# Power.net
KiCad netlist of a schematic drawn in Altium Designer
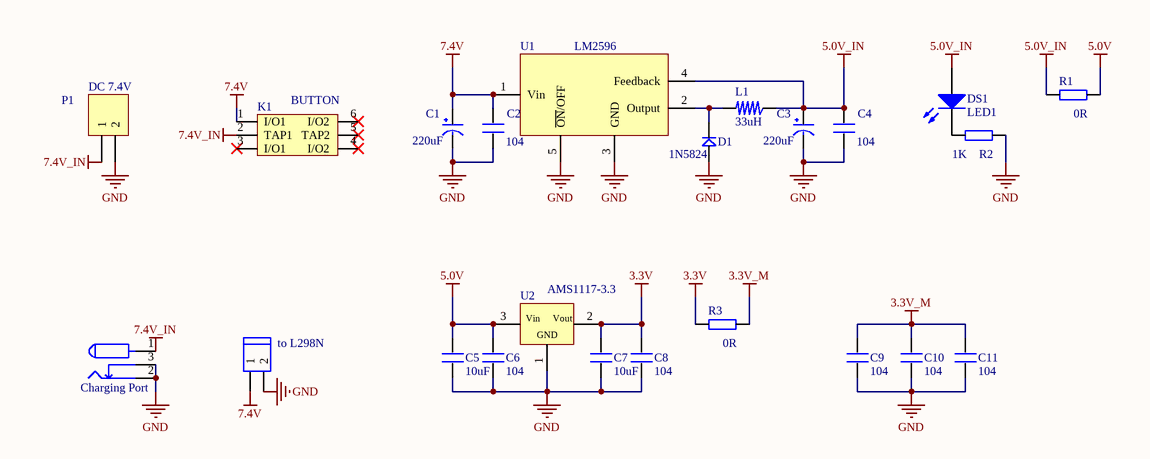
[diagram p0: Power.SchDoc]

(export (version "E")
  (design (tool "Eeschema 10.0.6"))
  (components
    (comp (ref "C1")
      (value "220uF")
      (footprint "CC6.56.5")
      (libsource (lib "WarShip V3 STM32103封装库") (part "CAP"))
    )
    (comp (ref "C2") (value "104") (footprint "0603P") (libsource (lib "WarShip V3 STM32103封装库") (part "C")))
    (comp (ref "C3")
      (value "220uF")
      (footprint "CC6.56.5")
      (libsource (lib "WarShip V3 STM32103封装库") (part "CAP"))
    )
    (comp (ref "C4") (value "104") (footprint "0603P") (libsource (lib "WarShip V3 STM32103封装库") (part "C")))
    (comp (ref "C5") (value "10uF") (footprint "0603P") (libsource (lib "WarShip V3 STM32103封装库") (part "C")))
    (comp (ref "C6") (value "104") (footprint "0603P") (libsource (lib "WarShip V3 STM32103封装库") (part "C")))
    (comp (ref "C7") (value "10uF") (footprint "0603P") (libsource (lib "WarShip V3 STM32103封装库") (part "C")))
    (comp (ref "C8") (value "104") (footprint "0603P") (libsource (lib "WarShip V3 STM32103封装库") (part "C")))
    (comp (ref "C9") (value "104") (footprint "0603P") (libsource (lib "WarShip V3 STM32103封装库") (part "C")))
    (comp (ref "C10") (value "104") (footprint "0603P") (libsource (lib "WarShip V3 STM32103封装库") (part "C")))
    (comp (ref "C11") (value "104") (footprint "0603P") (libsource (lib "WarShip V3 STM32103封装库") (part "C")))
    (comp (ref "D1")
      (value "1N5824")
      (footprint "DIODE_SOP")
      (libsource (lib "WarShip V3 STM32103封装库") (part "D"))
    )
    (comp (ref "DC_IN1")
      (value "Charging Port")
      (footprint "DC10B")
      (libsource (lib "WarShip V3 STM32103封装库") (part "POW"))
    )
    (comp (ref "DS1")
      (value "LED1")
      (footprint "SMDLED")
      (description "Typical RED, GREEN, YELLOW, AMBER GaAs LED")
      (fields (field (name "PUBLISHER") "Altium Limited"))
      (libsource (lib "WarShip V3 STM32103封装库") (part "LED2"))
    )
    (comp (ref "K1")
      (value "BUTTON")
      (footprint "BTN8.5*8.5")
      (libsource (lib "WarShip V3 STM32103封装库") (part "BUTTON"))
    )
    (comp (ref "L1") (value "33uH") (footprint "CD54") (libsource (lib "Zink_LIB") (part "L")))
    (comp (ref "P1")
      (value "DC 7.4V")
      (footprint "XH2.54-2P")
      (description "Header, 2-Pin")
      (libsource (lib "Zink_LIB") (part "Header-2"))
    )
    (comp (ref "R1") (value "0R") (footprint "0603P") (libsource (lib "WarShip V3 STM32103封装库") (part "R")))
    (comp (ref "R2") (value "1K") (footprint "0603P") (libsource (lib "WarShip V3 STM32103封装库") (part "R")))
    (comp (ref "R3") (value "0R") (footprint "0603P") (libsource (lib "WarShip V3 STM32103封装库") (part "R")))
    (comp (ref "RS1")
      (value "to L298N")
      (footprint "HEAD2L-0.8")
      (libsource (lib "WarShip V3 STM32103封装库") (part "HEAD2"))
    )
    (comp (ref "U1")
      (value "LM2596")
      (footprint "TO-263-5")
      (description "LM2596 - 5.0")
      (libsource (lib "Zink_LIB") (part "LM2596"))
    )
    (comp (ref "U2")
      (value "AMS1117-3.3")
      (footprint "SOT223-4L")
      (libsource (lib "Zink_LIB") (part "AMS1117"))
    )
  )
  (nets
    (net (code "1") (name "3.3V") (class "Default")
      (node (ref "C7") (pin "2") (pintype "passive"))
      (node (ref "C8") (pin "2") (pintype "passive"))
      (node (ref "R3") (pin "1") (pintype "passive"))
      (node (ref "U2") (pin "2") (pinfunction "Vout_2") (pintype "passive"))
    )
    (net (code "2") (name "3.3V_M") (class "Default")
      (node (ref "C10") (pin "2") (pintype "passive"))
      (node (ref "C11") (pin "2") (pintype "passive"))
      (node (ref "C9") (pin "2") (pintype "passive"))
      (node (ref "R3") (pin "2") (pintype "passive"))
    )
    (net (code "3") (name "5.0V") (class "Default")
      (node (ref "C5") (pin "2") (pintype "passive"))
      (node (ref "C6") (pin "2") (pintype "passive"))
      (node (ref "R1") (pin "2") (pintype "passive"))
      (node (ref "U2") (pin "3") (pinfunction "Vin_3") (pintype "passive"))
    )
    (net (code "4") (name "5.0V_IN") (class "Default")
      (node (ref "C3") (pin "1") (pinfunction "VCC_1") (pintype "passive"))
      (node (ref "C4") (pin "2") (pintype "passive"))
      (node (ref "DS1") (pin "1") (pinfunction "A_1") (pintype "passive"))
      (node (ref "L1") (pin "2") (pinfunction "2_2") (pintype "passive"))
      (node (ref "R1") (pin "1") (pintype "passive"))
      (node (ref "U1") (pin "4") (pinfunction "Feedback_4") (pintype "passive"))
    )
    (net (code "5") (name "7.4V") (class "Default")
      (node (ref "C1") (pin "1") (pinfunction "VCC_1") (pintype "passive"))
      (node (ref "C2") (pin "2") (pintype "passive"))
      (node (ref "K1") (pin "1") (pinfunction "I/O1_1") (pintype "passive"))
      (node (ref "RS1") (pin "1") (pinfunction "1_1") (pintype "passive"))
      (node (ref "U1") (pin "1") (pinfunction "Vin_1") (pintype "passive"))
    )
    (net (code "6") (name "7.4V_IN") (class "Default")
      (node (ref "DC_IN1") (pin "1") (pintype "passive"))
      (node (ref "K1") (pin "2") (pinfunction "TAP1_2") (pintype "passive"))
      (node (ref "P1") (pin "1") (pinfunction "1_1") (pintype "passive"))
    )
    (net (code "7") (name "GND") (class "Default")
      (node (ref "C1") (pin "2") (pinfunction "GND_2") (pintype "passive"))
      (node (ref "C10") (pin "1") (pintype "passive"))
      (node (ref "C11") (pin "1") (pintype "passive"))
      (node (ref "C2") (pin "1") (pintype "passive"))
      (node (ref "C3") (pin "2") (pinfunction "GND_2") (pintype "passive"))
      (node (ref "C4") (pin "1") (pintype "passive"))
      (node (ref "C5") (pin "1") (pintype "passive"))
      (node (ref "C6") (pin "1") (pintype "passive"))
      (node (ref "C7") (pin "1") (pintype "passive"))
      (node (ref "C8") (pin "1") (pintype "passive"))
      (node (ref "C9") (pin "1") (pintype "passive"))
      (node (ref "D1") (pin "1") (pintype "passive"))
      (node (ref "DC_IN1") (pin "2") (pintype "passive"))
      (node (ref "DC_IN1") (pin "3") (pintype "passive"))
      (node (ref "P1") (pin "2") (pinfunction "2_2") (pintype "passive"))
      (node (ref "R2") (pin "2") (pintype "passive"))
      (node (ref "RS1") (pin "2") (pinfunction "2_2") (pintype "passive"))
      (node (ref "U1") (pin "3") (pinfunction "GND_3") (pintype "passive"))
      (node (ref "U1") (pin "5") (pinfunction "~{ON}/OFF_5") (pintype "passive"))
      (node (ref "U2") (pin "1") (pinfunction "GND_1") (pintype "passive"))
    )
    (net (code "8") (name "Net-(DS1-K)") (class "Default")
      (node (ref "DS1") (pin "2") (pinfunction "K_2") (pintype "passive"))
      (node (ref "R2") (pin "1") (pintype "passive"))
    )
    (net (code "9") (name "Net-(U1-Output)") (class "Default")
      (node (ref "D1") (pin "2") (pintype "passive"))
      (node (ref "L1") (pin "1") (pinfunction "1_1") (pintype "passive"))
      (node (ref "U1") (pin "2") (pinfunction "Output_2") (pintype "passive"))
    )
    (net (code "10") (name "unconnected-(K1-I{slash}O1-Pad3)") (class "Default")
      (node (ref "K1") (pin "3") (pinfunction "I/O1_3") (pintype "passive+no_connect"))
    )
    (net (code "11") (name "unconnected-(K1-I{slash}O2-Pad4)") (class "Default")
      (node (ref "K1") (pin "4") (pinfunction "I/O2_4") (pintype "passive+no_connect"))
    )
    (net (code "12") (name "unconnected-(K1-I{slash}O2-Pad6)") (class "Default")
      (node (ref "K1") (pin "6") (pinfunction "I/O2_6") (pintype "passive+no_connect"))
    )
    (net (code "13") (name "unconnected-(K1-TAP2-Pad5)") (class "Default")
      (node (ref "K1") (pin "5") (pinfunction "TAP2_5") (pintype "passive+no_connect"))
    )
  )
)
